# SH1_-_CONNECTORS_AND_POWER.net
KiCad netlist of a schematic drawn in Altium Designer
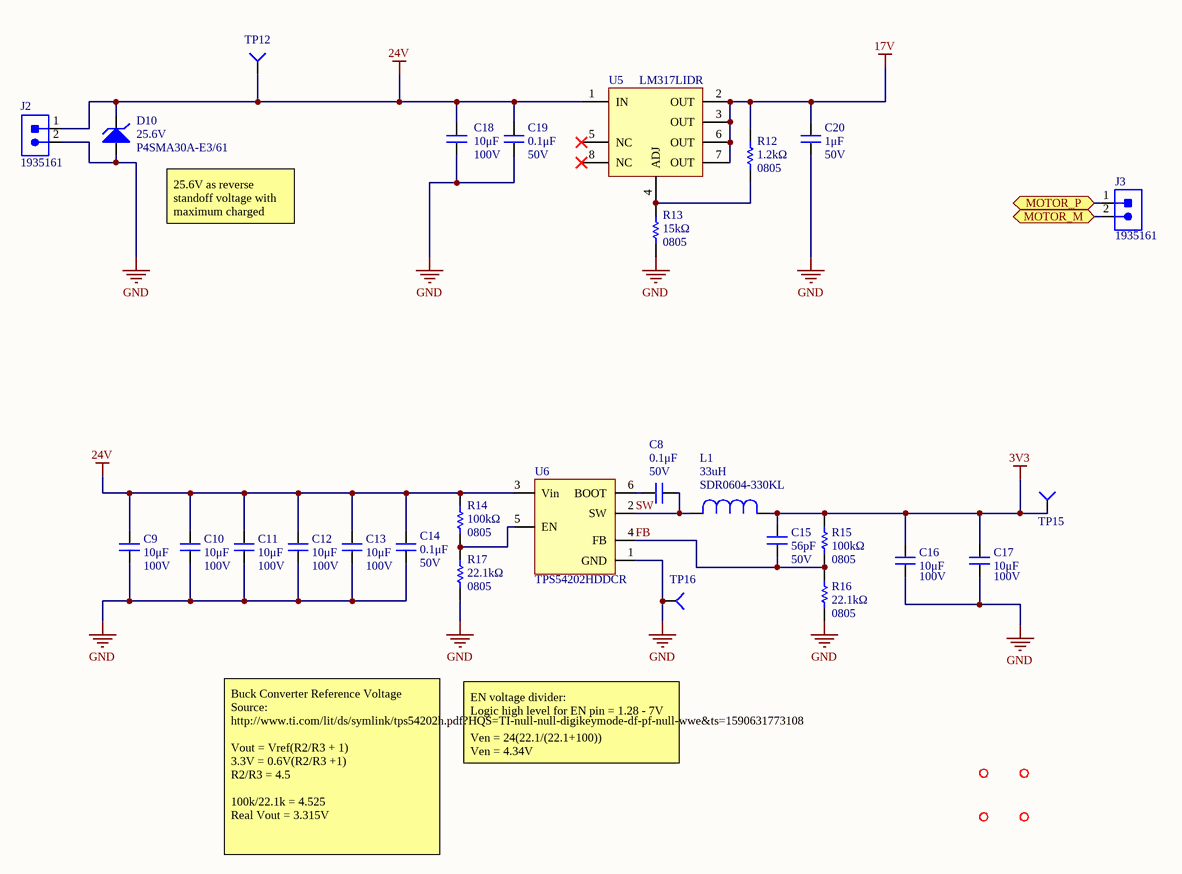
[diagram p0: SH1 - CONNECTORS AND POWER.SchDoc]

(export (version "E")
  (design (tool "Eeschema 10.0.6"))
  (components
    (comp (ref "C8")
      (value "0.1μF")
      (footprint "CAP2012")
      (description "CAP CER 0.1UF 50V X7R 0805")
      (fields (field (name "TOLERANCE") "10%") (field (name "VOLTAGE RATING") "50V"))
      (libsource (lib "UWRT_Schematic_Library_2020") (part "CAP_0.1uF_50V_0805"))
    )
    (comp (ref "C9")
      (value "10μF")
      (footprint "CAP1210")
      (description "CAP CER 10uF 100V X7S 10% 1210")
      (fields
        (field (name "TOLERANCE") "10%")
        (field (name "VOLTAGE RATING") "100V")
        (field (name "Comment") "CAP_10uF_100V_1210")
      )
      (libsource (lib "UWRT_Schematic_Library_2020") (part "CAP_10uF_100V_1210"))
    )
    (comp (ref "C10")
      (value "10μF")
      (footprint "CAP1210")
      (description "CAP CER 10uF 100V X7S 10% 1210")
      (fields
        (field (name "TOLERANCE") "10%")
        (field (name "VOLTAGE RATING") "100V")
        (field (name "Comment") "CAP_10uF_100V_1210")
      )
      (libsource (lib "UWRT_Schematic_Library_2020") (part "CAP_10uF_100V_1210"))
    )
    (comp (ref "C11")
      (value "10μF")
      (footprint "CAP1210")
      (description "CAP CER 10uF 100V X7S 10% 1210")
      (fields
        (field (name "TOLERANCE") "10%")
        (field (name "VOLTAGE RATING") "100V")
        (field (name "Comment") "CAP_10uF_100V_1210")
      )
      (libsource (lib "UWRT_Schematic_Library_2020") (part "CAP_10uF_100V_1210"))
    )
    (comp (ref "C12")
      (value "10μF")
      (footprint "CAP1210")
      (description "CAP CER 10uF 100V X7S 10% 1210")
      (fields
        (field (name "VOLTAGE RATING") "100V")
        (field (name "TOLERANCE") "10%")
        (field (name "Comment") "CAP_10uF_100V_1210")
      )
      (libsource (lib "UWRT_Schematic_Library_2020") (part "CAP_10uF_100V_1210"))
    )
    (comp (ref "C13")
      (value "10μF")
      (footprint "CAP1210")
      (description "CAP CER 10uF 100V X7S 10% 1210")
      (fields
        (field (name "VOLTAGE RATING") "100V")
        (field (name "TOLERANCE") "10%")
        (field (name "Comment") "CAP_10uF_100V_1210")
      )
      (libsource (lib "UWRT_Schematic_Library_2020") (part "CAP_10uF_100V_1210"))
    )
    (comp (ref "C14")
      (value "0.1μF")
      (footprint "CAP2012")
      (description "CAP CER 0.1UF 50V X7R 0805")
      (fields (field (name "TOLERANCE") "10%") (field (name "VOLTAGE RATING") "50V"))
      (libsource (lib "UWRT_Schematic_Library_2020") (part "CAP_0.1uF_50V_0805"))
    )
    (comp (ref "C15")
      (value "56pF")
      (footprint "CAP2012")
      (description "CAP CER 56PF 50V C0G/NP0")
      (fields
        (field (name "TOLERANCE") "1%")
        (field (name "VOLTAGE RATING") "50V")
        (field (name "Comment") "CAP_56pF_50V_0805")
      )
      (libsource (lib "UWRT_Schematic_Library_2020") (part "CAP_56pF_50V_0805"))
    )
    (comp (ref "C16")
      (value "10μF")
      (footprint "CAP1210")
      (description "CAP CER 10uF 100V X7S 10% 1210")
      (fields
        (field (name "TOLERANCE") "10%")
        (field (name "VOLTAGE RATING") "100V")
        (field (name "Comment") "CAP_10uF_100V_1210")
      )
      (libsource (lib "UWRT_Schematic_Library_2020") (part "CAP_10uF_100V_1210"))
    )
    (comp (ref "C17")
      (value "10μF")
      (footprint "CAP1210")
      (description "CAP CER 10uF 100V X7S 10% 1210")
      (fields
        (field (name "TOLERANCE") "10%")
        (field (name "VOLTAGE RATING") "100V")
        (field (name "Comment") "CAP_10uF_100V_1210")
      )
      (libsource (lib "UWRT_Schematic_Library_2020") (part "CAP_10uF_100V_1210"))
    )
    (comp (ref "C18")
      (value "10μF")
      (footprint "CAP1210")
      (description "CAP CER 10uF 100V X7S 10% 1210")
      (fields
        (field (name "TOLERANCE") "10%")
        (field (name "VOLTAGE RATING") "100V")
        (field (name "Comment") "CAP_10uF_100V_1210")
      )
      (libsource (lib "UWRT_Schematic_Library_2020") (part "CAP_10uF_100V_1210"))
    )
    (comp (ref "C19")
      (value "0.1μF")
      (footprint "CAP2012")
      (description "CAP CER 0.1UF 50V X7R 0805")
      (fields (field (name "TOLERANCE") "10%") (field (name "VOLTAGE RATING") "50V"))
      (libsource (lib "UWRT_Schematic_Library_2020") (part "CAP_0.1uF_50V_0805"))
    )
    (comp (ref "C20")
      (value "1μF")
      (footprint "CAP2012")
      (description "CAP CER 1UF 50V X7R 0805")
      (fields (field (name "VOLTAGE RATING") "50V") (field (name "Comment") "CAP_1uF_50V_0805"))
      (libsource (lib "UWRT_Schematic_Library_2020") (part "CAP_1uF_50V_0805"))
    )
    (comp (ref "D10")
      (value "P4SMA30A-E3/61")
      (footprint "DO-214AC_UNI")
      (description "TVS DIODE, 400W, 25.6V, UNI, DO-214AC")
      (fields
        (field (name "REVERSE STANDOFF VOLTAGE") "25.6V")
        (field (name "MANUFACTURER PART NUMBER 1") "P4SMA30A-E3/61")
      )
      (libsource (lib "UWRT_Schematic_Library_2020") (part "P4SMA30A-E3/61"))
    )
    (comp (ref "J2")
      (value "1935161")
      (footprint "1935161")
      (description "TERM BLK 2POS SIDE ENTRY 5MM")
      (fields (field (name "VOLTAGE") "300V"))
      (libsource (lib "") (part "CON_2M_TERM_1"))
    )
    (comp (ref "J3")
      (value "1935161")
      (footprint "1935161")
      (description "TERM BLK 2POS SIDE ENTRY 5MM")
      (fields (field (name "VOLTAGE") "300V"))
      (libsource (lib "UWRT_Schematic_Library_2020") (part "CON_2M_TERM"))
    )
    (comp (ref "L1")
      (value "IND_33uH_880mA")
      (footprint "IND_BOURNS_SDR0604")
      (description "IND, 33uH, 10%, 1 Element, Ferrite-Core, SMD")
      (fields
        (field (name "TOLERANCE") "10%")
        (field (name "MANUFACTURER PART NUMBER 1") "SDR0604-330KL")
        (field (name "INDUCTANCE") "33uH")
      )
      (libsource (lib "UWRT_Schematic_Library_2020") (part "IND_33uH_880mA"))
    )
    (comp (ref "MH1")
      (value "MOUNTING_HOLES")
      (footprint "MOUNTING_HOLE")
      (description "6cm x 6cm")
      (libsource (lib "UWRT_Schematic_Library_2020") (part "MOUNTING_HOLES"))
    )
    (comp (ref "MH2")
      (value "MOUNTING_HOLES")
      (footprint "MOUNTING_HOLE")
      (description "6cm x 6cm")
      (libsource (lib "UWRT_Schematic_Library_2020") (part "MOUNTING_HOLES"))
    )
    (comp (ref "MH3")
      (value "MOUNTING_HOLES")
      (footprint "MOUNTING_HOLE")
      (description "6cm x 6cm")
      (libsource (lib "UWRT_Schematic_Library_2020") (part "MOUNTING_HOLES"))
    )
    (comp (ref "MH4")
      (value "MOUNTING_HOLES")
      (footprint "MOUNTING_HOLE")
      (description "6cm x 6cm")
      (libsource (lib "UWRT_Schematic_Library_2020") (part "MOUNTING_HOLES"))
    )
    (comp (ref "R12")
      (value "1.2kΩ")
      (footprint "RESC2012X60N")
      (description "RES 1.2K OHM 1% 1/8W 0805")
      (fields
        (field (name "TOLERANCE") "1%")
        (field (name "CASE CODE (IMPERIAL)") "0805")
        (field (name "Comment") "RES_1.2kΩ_0805")
      )
      (libsource (lib "UWRT_Schematic_Library_2020") (part "RES_1.2kΩ_0805_1%"))
    )
    (comp (ref "R13")
      (value "15kΩ")
      (footprint "RESC2012X60N")
      (description "RES 15K OHM 1% 1/8W 0805")
      (fields
        (field (name "TOLERANCE") "1%")
        (field (name "CASE CODE (IMPERIAL)") "0805")
        (field (name "Comment") "RES_15Ω_0805")
      )
      (libsource (lib "UWRT_Schematic_Library_2020") (part "RES_15kΩ_0805_1%"))
    )
    (comp (ref "R14")
      (value "RES_100kΩ_0805")
      (footprint "RESC2012X60N")
      (description "RES 100K OHM 0.5% 1/8W 0805")
      (fields
        (field (name "CASE CODE (IMPERIAL)") "0805")
        (field (name "TOLERANCE") "0.5%")
        (field (name "RESISTANCE") "100kΩ")
      )
      (libsource (lib "UWRT_Schematic_Library_2020") (part "RES_100kΩ_0805_0.5%"))
    )
    (comp (ref "R15")
      (value "RES_100kΩ_0805")
      (footprint "RESC2012X60N")
      (description "RES 100K OHM 0.5% 1/8W 0805")
      (fields
        (field (name "CASE CODE (IMPERIAL)") "0805")
        (field (name "TOLERANCE") "0.5%")
        (field (name "RESISTANCE") "100kΩ")
      )
      (libsource (lib "UWRT_Schematic_Library_2020") (part "RES_100kΩ_0805_0.5%"))
    )
    (comp (ref "R16")
      (value "RES_22.1kΩ_0805")
      (footprint "RESC2012X60N")
      (description "RES 22.1K OHM 1% 1/8W 0805")
      (fields
        (field (name "TOLERANCE") "1%")
        (field (name "CASE CODE (IMPERIAL)") "0805")
        (field (name "RESISTANCE") "22.1kΩ")
      )
      (libsource (lib "UWRT_Schematic_Library_2020") (part "RES_22.1kΩ_0805_1%"))
    )
    (comp (ref "R17")
      (value "RES_22.1kΩ_0805")
      (footprint "RESC2012X60N")
      (description "RES 22.1K OHM 1% 1/8W 0805")
      (fields
        (field (name "TOLERANCE") "1%")
        (field (name "CASE CODE (IMPERIAL)") "0805")
        (field (name "RESISTANCE") "22.1kΩ")
      )
      (libsource (lib "UWRT_Schematic_Library_2020") (part "RES_22.1kΩ_0805_1%"))
    )
    (comp (ref "TP12")
      (value "TESTPOINT_SMD_LOOP")
      (footprint "S1751-46R")
      (description "PC TEST POINT SMD")
      (libsource (lib "UWRT_Schematic_Library_2020") (part "TESTPOINT_SMD_LOOP"))
    )
    (comp (ref "TP15")
      (value "TESTPOINT_SMD_LOOP")
      (footprint "S1751-46R")
      (description "PC TEST POINT SMD")
      (libsource (lib "UWRT_Schematic_Library_2020") (part "TESTPOINT_SMD_LOOP"))
    )
    (comp (ref "TP16")
      (value "TESTPOINT_SMD_LOOP")
      (footprint "S1751-46R")
      (description "PC TEST POINT SMD")
      (libsource (lib "UWRT_Schematic_Library_2020") (part "TESTPOINT_SMD_LOOP"))
    )
    (comp (ref "U5")
      (value "LM317LIDR")
      (footprint "LM317LIDR")
      (description "IC REG LIN POS ADJ 100MA 8SOIC")
      (libsource (lib "UWRT_Schematic_Library_2020") (part "LDO_ADJ_100mA"))
    )
    (comp (ref "U6")
      (value "TPS54202HDDCR")
      (footprint "SOT23-6")
      (description "IC REG BUCK ADJ 2A TSOT23-6")
      (fields (field (name "MANUFACTURER PART NUMBER 1") "TPS54202HDDCR"))
      (libsource (lib "UWRT_Schematic_Library_2020") (part "TPS54202HDDCR"))
    )
  )
  (nets
    (net (code "1") (name "/FB") (class "Default")
      (node (ref "C15") (pin "1") (pinfunction "1_1") (pintype "passive"))
      (node (ref "R15") (pin "1") (pinfunction "1_1") (pintype "passive"))
      (node (ref "R16") (pin "2") (pinfunction "2_2") (pintype "passive"))
      (node (ref "U6") (pin "4") (pinfunction "FB_4") (pintype "passive"))
    )
    (net (code "2") (name "/MOTOR_M") (class "Default")
      (node (ref "J3") (pin "2") (pinfunction "2_2") (pintype "passive"))
    )
    (net (code "3") (name "/MOTOR_P") (class "Default")
      (node (ref "J3") (pin "1") (pinfunction "1_1") (pintype "passive"))
    )
    (net (code "4") (name "/SW") (class "Default")
      (node (ref "C8") (pin "2") (pinfunction "2_2") (pintype "passive"))
      (node (ref "L1") (pin "2") (pinfunction "2_2") (pintype "passive"))
      (node (ref "U6") (pin "2") (pinfunction "SW_2") (pintype "passive"))
    )
    (net (code "5") (name "3V3") (class "Default")
      (node (ref "C15") (pin "2") (pinfunction "2_2") (pintype "passive"))
      (node (ref "C16") (pin "2") (pinfunction "2_2") (pintype "passive"))
      (node (ref "C17") (pin "2") (pinfunction "2_2") (pintype "passive"))
      (node (ref "L1") (pin "1") (pinfunction "1_1") (pintype "passive"))
      (node (ref "R15") (pin "2") (pinfunction "2_2") (pintype "passive"))
      (node (ref "TP15") (pin "1") (pinfunction "=value_1") (pintype "passive"))
    )
    (net (code "6") (name "17V") (class "Default")
      (node (ref "C20") (pin "2") (pinfunction "2_2") (pintype "passive"))
      (node (ref "R12") (pin "2") (pinfunction "2_2") (pintype "passive"))
      (node (ref "U5") (pin "2") (pinfunction "OUT_2") (pintype "power_in"))
      (node (ref "U5") (pin "3") (pinfunction "OUT_3") (pintype "power_in"))
      (node (ref "U5") (pin "6") (pinfunction "OUT_6") (pintype "power_in"))
      (node (ref "U5") (pin "7") (pinfunction "OUT_7") (pintype "power_in"))
    )
    (net (code "7") (name "24V") (class "Default")
      (node (ref "C10") (pin "2") (pinfunction "2_2") (pintype "passive"))
      (node (ref "C11") (pin "2") (pinfunction "2_2") (pintype "passive"))
      (node (ref "C12") (pin "2") (pinfunction "2_2") (pintype "passive"))
      (node (ref "C13") (pin "2") (pinfunction "2_2") (pintype "passive"))
      (node (ref "C14") (pin "2") (pinfunction "2_2") (pintype "passive"))
      (node (ref "C18") (pin "2") (pinfunction "2_2") (pintype "passive"))
      (node (ref "C19") (pin "2") (pinfunction "2_2") (pintype "passive"))
      (node (ref "C9") (pin "2") (pinfunction "2_2") (pintype "passive"))
      (node (ref "D10") (pin "2") (pinfunction "2_2") (pintype "passive"))
      (node (ref "J2") (pin "1") (pinfunction "1_1") (pintype "passive"))
      (node (ref "R14") (pin "2") (pinfunction "2_2") (pintype "passive"))
      (node (ref "TP12") (pin "1") (pinfunction "=value_1") (pintype "passive"))
      (node (ref "U5") (pin "1") (pinfunction "IN_1") (pintype "power_in"))
      (node (ref "U6") (pin "3") (pinfunction "Vin_3") (pintype "passive"))
    )
    (net (code "8") (name "GND") (class "Default")
      (node (ref "C10") (pin "1") (pinfunction "1_1") (pintype "passive"))
      (node (ref "C11") (pin "1") (pinfunction "1_1") (pintype "passive"))
      (node (ref "C12") (pin "1") (pinfunction "1_1") (pintype "passive"))
      (node (ref "C13") (pin "1") (pinfunction "1_1") (pintype "passive"))
      (node (ref "C14") (pin "1") (pinfunction "1_1") (pintype "passive"))
      (node (ref "C16") (pin "1") (pinfunction "1_1") (pintype "passive"))
      (node (ref "C17") (pin "1") (pinfunction "1_1") (pintype "passive"))
      (node (ref "C18") (pin "1") (pinfunction "1_1") (pintype "passive"))
      (node (ref "C19") (pin "1") (pinfunction "1_1") (pintype "passive"))
      (node (ref "C20") (pin "1") (pinfunction "1_1") (pintype "passive"))
      (node (ref "C9") (pin "1") (pinfunction "1_1") (pintype "passive"))
      (node (ref "D10") (pin "1") (pinfunction "1_1") (pintype "passive"))
      (node (ref "J2") (pin "2") (pinfunction "2_2") (pintype "passive"))
      (node (ref "R13") (pin "1") (pinfunction "1_1") (pintype "passive"))
      (node (ref "R16") (pin "1") (pinfunction "1_1") (pintype "passive"))
      (node (ref "R17") (pin "1") (pinfunction "1_1") (pintype "passive"))
      (node (ref "TP16") (pin "1") (pinfunction "=value_1") (pintype "passive"))
      (node (ref "U6") (pin "1") (pinfunction "GND_1") (pintype "passive"))
    )
    (net (code "9") (name "Net-(U5-ADJ)") (class "Default")
      (node (ref "R12") (pin "1") (pinfunction "1_1") (pintype "passive"))
      (node (ref "R13") (pin "2") (pinfunction "2_2") (pintype "passive"))
      (node (ref "U5") (pin "4") (pinfunction "ADJ_4") (pintype "power_in"))
    )
    (net (code "10") (name "Net-(U6-BOOT)") (class "Default")
      (node (ref "C8") (pin "1") (pinfunction "1_1") (pintype "passive"))
      (node (ref "U6") (pin "6") (pinfunction "BOOT_6") (pintype "passive"))
    )
    (net (code "11") (name "Net-(U6-EN)") (class "Default")
      (node (ref "R14") (pin "1") (pinfunction "1_1") (pintype "passive"))
      (node (ref "R17") (pin "2") (pinfunction "2_2") (pintype "passive"))
      (node (ref "U6") (pin "5") (pinfunction "EN_5") (pintype "passive"))
    )
    (net (code "12") (name "unconnected-(U5-NC-Pad5)") (class "Default")
      (node (ref "U5") (pin "5") (pinfunction "NC_5") (pintype "power_in+no_connect"))
    )
    (net (code "13") (name "unconnected-(U5-NC-Pad8)") (class "Default")
      (node (ref "U5") (pin "8") (pinfunction "NC_8") (pintype "power_in+no_connect"))
    )
  )
)
